# 105358-3SC001-02_IO_BRD.net
KiCad netlist of a schematic drawn in Altium Designer
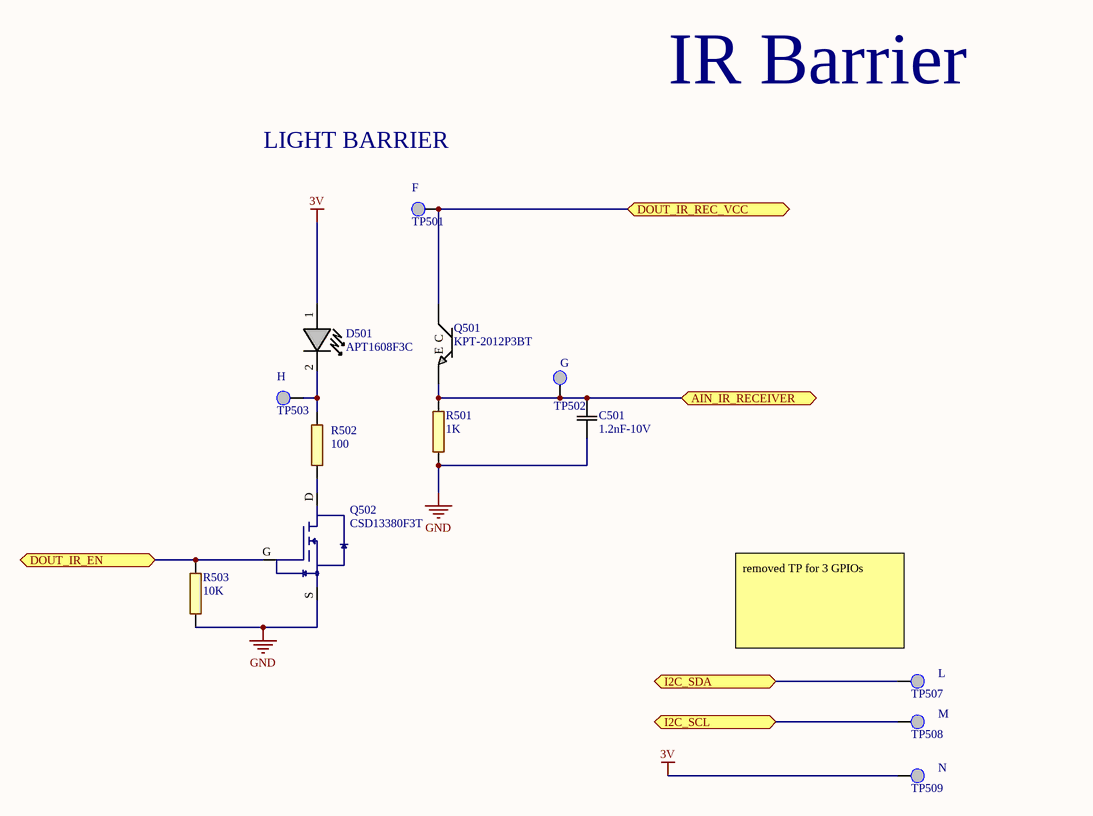
[diagram p0: 105358-3SC001-02_IO_BRD.SchDoc]

(export (version "E")
  (design (tool "Eeschema 10.0.6"))
  (components
    (comp (ref "C501")
      (value "1.2nF-10V")
      (footprint "0402C_HIGH_DENSITY")
      (description "1.2nF ±10% 10V U2J Ceramic Capacitor 0402")
      (fields
        (field (name "MANUFACTURER PART NUMBER") "GRM1557U1A122JA01D")
        (field (name "MANUFACTURER") "Murata Electronics North America")
      )
      (libsource (lib "ConnectMedical") (part "0402C-1.2nF-10V"))
    )
    (comp (ref "D501")
      (value "APT1608F3C")
      (footprint "APT1608F3C")
      (description "0603 INFRARED DIODE")
      (fields
        (field (name "MANUFACTURER") "Kingbright")
        (field (name "DIGI-KEY PART NUMBER") "754-1433-1-ND")
      )
      (libsource (lib "ConnectMedical") (part "APT1608F3C"))
    )
    (comp (ref "Q501")
      (value "KPT-2012P3BT")
      (footprint "APT2012P3BT")
      (description "0805 PHOTOTRANSISTOR")
      (fields
        (field (name "MANUFACTURER") "Kingbright")
        (field (name "DIGI-KEY PART NUMBER") "754-1436-1-ND")
      )
      (libsource (lib "ConnectMedical") (part "APT2012P3BT"))
    )
    (comp (ref "Q502")
      (value "CSD13380F3T")
      (footprint "CSD13380F3-DFN40P69X35-3L")
      (description "12V N-CHANNEL FEMTOFET MOSFET")
      (fields (field (name "MANUFACTURER") "Texas Instruments"))
      (libsource (lib "ConnectMedical") (part "CSD13380F3T"))
    )
    (comp (ref "R501")
      (value "1K")
      (footprint "0402R-GENERIC")
      (description "RES SMD 1kOHM 1% 1/16W 0402")
      (fields (field (name "TOLERANCE") "1%") (field (name "POWER") "0.063W"))
      (libsource (lib "ConnectMedical") (part "0402R-1k OHM-1%-0.063W"))
    )
    (comp (ref "R502")
      (value "100")
      (footprint "0402R-GENERIC")
      (description "RES SMD 100OHM 1% 1/16W 0402")
      (fields (field (name "DIGI-KEY PART NUMBER") "311-100LRCT-ND") (field (name "MANUFACTURER") "Yageo"))
      (libsource (lib "ConnectMedical") (part "0402R-100 OHM-1%-0.063W"))
    )
    (comp (ref "R503")
      (value "10K")
      (footprint "0402R-GENERIC")
      (description "RES SMD 10kOHM 1% 1/16W 0402")
      (fields (field (name "DIGI-KEY PART NUMBER") "311-10.0KLRCT-ND") (field (name "MANUFACTURER") "Yageo"))
      (libsource (lib "ConnectMedical") (part "0402R-10k OHM-1%-0.063W"))
    )
    (comp (ref "TP501")
      (value "TEST POINT")
      (footprint "PAD TEST POINT")
      (description "Testing Poiny")
      (libsource (lib "ConnectMedical") (part "TEST POINT"))
    )
    (comp (ref "TP502")
      (value "TEST POINT")
      (footprint "PAD TEST POINT")
      (description "Testing Poiny")
      (libsource (lib "ConnectMedical") (part "TEST POINT"))
    )
    (comp (ref "TP503")
      (value "TEST POINT")
      (footprint "PAD TEST POINT")
      (description "Testing Poiny")
      (libsource (lib "ConnectMedical") (part "TEST POINT"))
    )
    (comp (ref "TP507")
      (value "TEST POINT")
      (footprint "PAD TEST POINT")
      (description "Testing Poiny")
      (libsource (lib "ConnectMedical") (part "TEST POINT"))
    )
    (comp (ref "TP508")
      (value "TEST POINT")
      (footprint "PAD TEST POINT")
      (description "Testing Poiny")
      (libsource (lib "ConnectMedical") (part "TEST POINT"))
    )
    (comp (ref "TP509")
      (value "TEST POINT")
      (footprint "PAD TEST POINT")
      (description "Testing Poiny")
      (libsource (lib "ConnectMedical") (part "TEST POINT"))
    )
  )
  (nets
    (net (code "1") (name "/AIN_IR_RECEIVER") (class "Default")
      (node (ref "C501") (pin "2") (pinfunction "2_2") (pintype "passive"))
      (node (ref "Q501") (pin "1") (pinfunction "E_1") (pintype "passive"))
      (node (ref "R501") (pin "1") (pintype "passive"))
      (node (ref "TP502") (pin "1") (pinfunction "Test_Point_1") (pintype "passive"))
    )
    (net (code "2") (name "/DOUT_IR_EN") (class "Default")
      (node (ref "Q502") (pin "G") (pinfunction "1_G") (pintype "passive"))
      (node (ref "R503") (pin "1") (pintype "passive"))
    )
    (net (code "3") (name "/DOUT_IR_REC_VCC") (class "Default")
      (node (ref "Q501") (pin "2") (pinfunction "C_2") (pintype "passive"))
      (node (ref "TP501") (pin "1") (pinfunction "Test_Point_1") (pintype "passive"))
    )
    (net (code "4") (name "/I2C_SCL") (class "Default")
      (node (ref "TP508") (pin "1") (pinfunction "Test_Point_1") (pintype "passive"))
    )
    (net (code "5") (name "/I2C_SDA") (class "Default")
      (node (ref "TP507") (pin "1") (pinfunction "Test_Point_1") (pintype "passive"))
    )
    (net (code "6") (name "3V") (class "Default")
      (node (ref "D501") (pin "1") (pinfunction "A_1") (pintype "passive"))
      (node (ref "TP509") (pin "1") (pinfunction "Test_Point_1") (pintype "passive"))
    )
    (net (code "7") (name "GND") (class "Default")
      (node (ref "C501") (pin "1") (pinfunction "1_1") (pintype "passive"))
      (node (ref "Q502") (pin "S") (pinfunction "2_S") (pintype "passive"))
      (node (ref "R501") (pin "2") (pintype "passive"))
      (node (ref "R503") (pin "2") (pintype "passive"))
    )
    (net (code "8") (name "Net-(D501-K)") (class "Default")
      (node (ref "D501") (pin "2") (pinfunction "K_2") (pintype "passive"))
      (node (ref "R502") (pin "1") (pintype "passive"))
      (node (ref "TP503") (pin "1") (pinfunction "Test_Point_1") (pintype "passive"))
    )
    (net (code "9") (name "Net-(Q502-3)") (class "Default")
      (node (ref "Q502") (pin "D") (pinfunction "3_D") (pintype "passive"))
      (node (ref "R502") (pin "2") (pintype "passive"))
    )
  )
)
